# Eagle_Moisture_Sensor.net
KiCad netlist of a schematic drawn in EAGLE
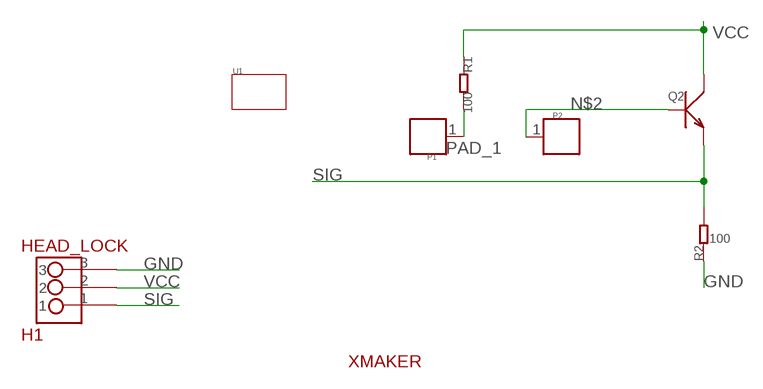
[diagram p0: schematic, sheet 1]

(export (version "E")
  (design (tool "Eeschema 10.0.6"))
  (components
    (comp (ref "H1")
      (value "HEAD_LOCK")
      (footprint "eagle-import:HEAD_LOCK")
      (libsource (lib "eagle-import") (part "HEAD_LOCK"))
    )
    (comp (ref "P1")
      (value "PAD.03")
      (footprint "eagle-import:1P-SMD-0.76X0.76")
      (libsource (lib "eagle-import") (part "PAD.03"))
    )
    (comp (ref "P2")
      (value "PAD.03")
      (footprint "eagle-import:1P-SMD-0.76X0.76")
      (libsource (lib "eagle-import") (part "PAD.03"))
    )
    (comp (ref "Q2")
      (value "TRANSISTOR-NPN-SOT23''")
      (footprint "eagle-import:SOT23")
      (libsource (lib "eagle-import") (part "TRANSISTOR-NPN-SOT23''"))
    )
    (comp (ref "R1")
      (value "100")
      (footprint "eagle-import:0603")
      (libsource (lib "eagle-import") (part "R-0603"))
    )
    (comp (ref "R2")
      (value "100")
      (footprint "eagle-import:0603")
      (libsource (lib "eagle-import") (part "R-0603"))
    )
    (comp (ref "U$1")
      (value "XMAKERLOGO2")
      (footprint "eagle-import:XMAKERLOGO2")
      (libsource (lib "eagle-import") (part "XMAKERLOGO2"))
    )
    (comp (ref "U1")
      (value "TWIG'SPECIAL'")
      (footprint "eagle-import:3U-DIM-W_-DRILL-SPECIAL")
      (libsource (lib "eagle-import") (part "TWIG'SPECIAL'"))
    )
  )
  (nets
    (net (code "1") (name "/GND") (class "Default")
      (node (ref "H1") (pin "3") (pinfunction "3_3") (pintype "passive"))
      (node (ref "R2") (pin "1") (pinfunction "1_1") (pintype "passive"))
    )
    (net (code "2") (name "/N$2") (class "Default")
      (node (ref "P2") (pin "1") (pinfunction "P$1_1") (pintype "bidirectional"))
      (node (ref "Q2") (pin "1") (pinfunction "B_1") (pintype "passive"))
    )
    (net (code "3") (name "/PAD_1") (class "Default")
      (node (ref "P1") (pin "1") (pinfunction "P$1_1") (pintype "bidirectional"))
      (node (ref "R1") (pin "2") (pinfunction "2_2") (pintype "passive"))
    )
    (net (code "4") (name "/SIG") (class "Default")
      (node (ref "H1") (pin "1") (pinfunction "1_1") (pintype "passive"))
      (node (ref "Q2") (pin "2") (pinfunction "E_2") (pintype "passive"))
      (node (ref "R2") (pin "2") (pinfunction "2_2") (pintype "passive"))
    )
    (net (code "5") (name "/VCC") (class "Default")
      (node (ref "H1") (pin "2") (pinfunction "2_2") (pintype "passive"))
      (node (ref "Q2") (pin "3") (pinfunction "C_3") (pintype "passive"))
      (node (ref "R1") (pin "1") (pinfunction "1_1") (pintype "passive"))
    )
  )
)
